# SensorBoard_WiiCam.net
KiCad netlist of a schematic drawn in EAGLE
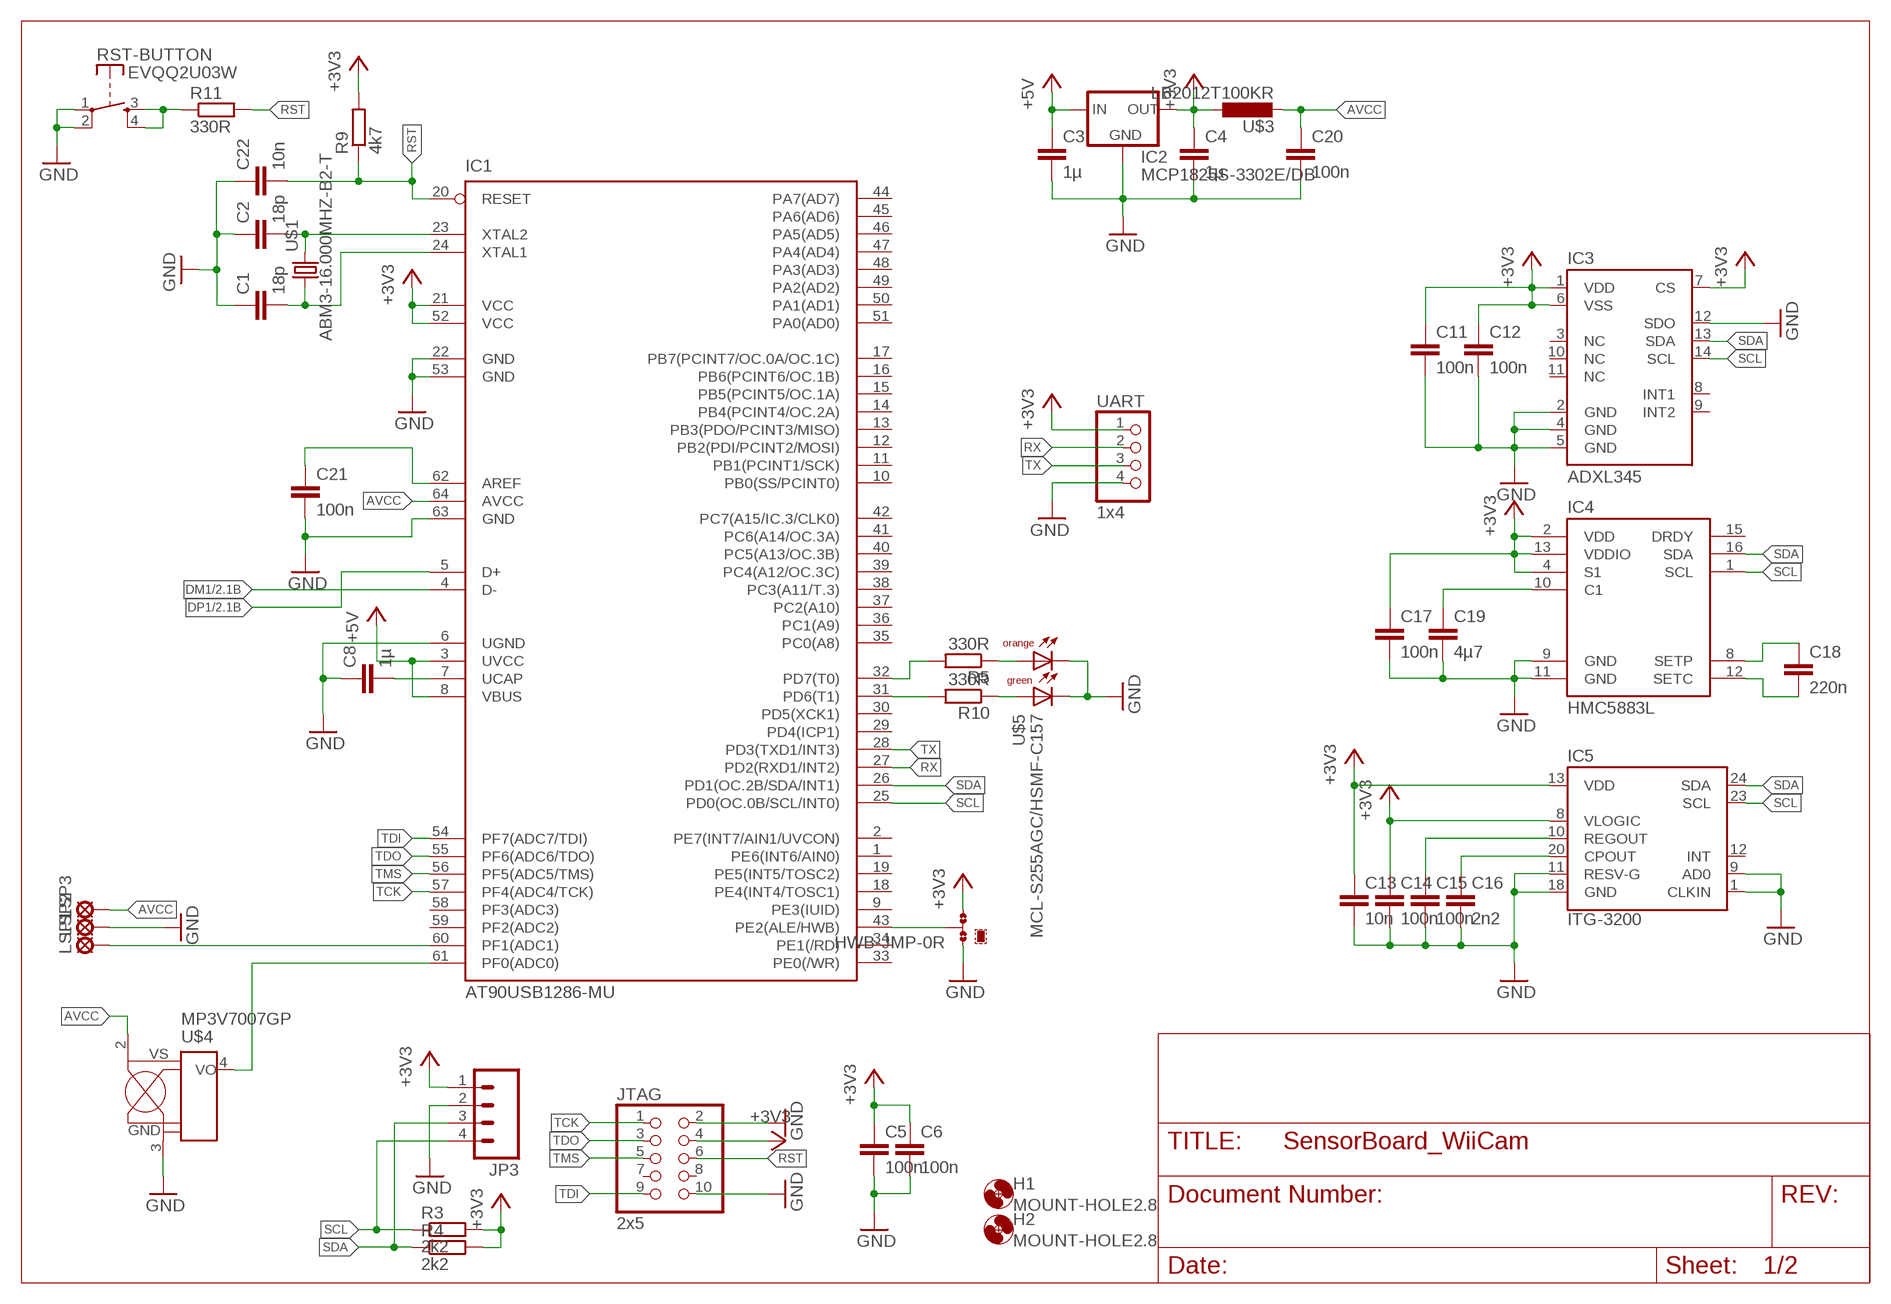
[diagram p0: schematic, sheet 1]
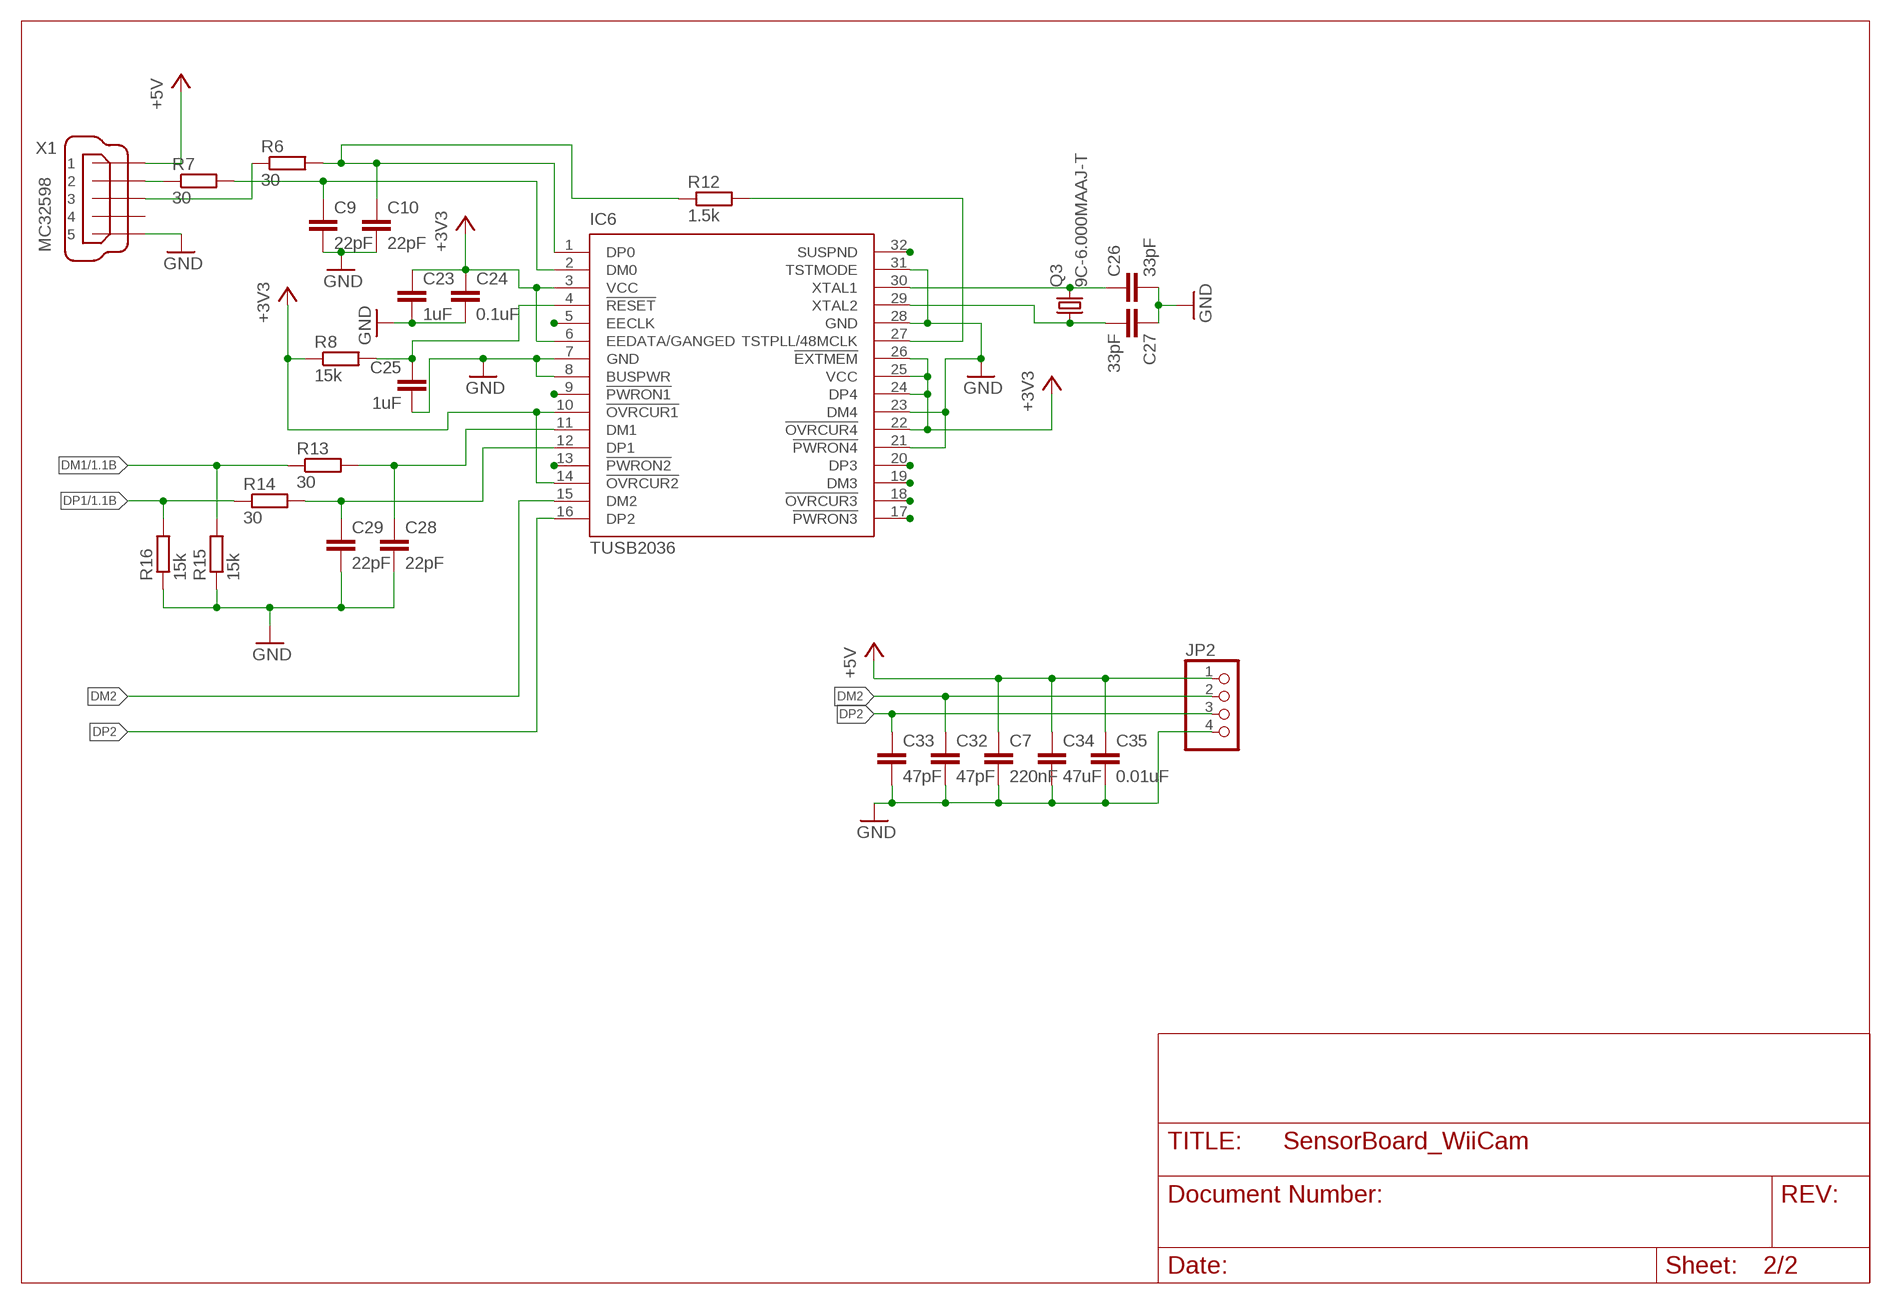
[diagram p1: schematic, sheet 2]

(export (version "E")
  (design (tool "Eeschema 10.0.6"))
  (components
    (comp (ref "C1")
      (value "18p")
      (footprint "eagle-import:C0603K")
      (libsource (lib "eagle-import") (part "C-EUC0603K"))
    )
    (comp (ref "C2")
      (value "18p")
      (footprint "eagle-import:C0603K")
      (libsource (lib "eagle-import") (part "C-EUC0603K"))
    )
    (comp (ref "C3")
      (value "1µ")
      (footprint "eagle-import:C0603K")
      (libsource (lib "eagle-import") (part "C-EUC0603K"))
    )
    (comp (ref "C4")
      (value "1µ")
      (footprint "eagle-import:C0603K")
      (libsource (lib "eagle-import") (part "C-EUC0603K"))
    )
    (comp (ref "C5")
      (value "100n")
      (footprint "eagle-import:C0603K")
      (libsource (lib "eagle-import") (part "C-EUC0603K"))
    )
    (comp (ref "C6")
      (value "100n")
      (footprint "eagle-import:C0603K")
      (libsource (lib "eagle-import") (part "C-EUC0603K"))
    )
    (comp (ref "C8")
      (value "1µ")
      (footprint "eagle-import:C0603K")
      (libsource (lib "eagle-import") (part "C-EUC0603K"))
    )
    (comp (ref "C11")
      (value "100n")
      (footprint "eagle-import:C0603K")
      (libsource (lib "eagle-import") (part "C-EUC0603K"))
    )
    (comp (ref "C12")
      (value "100n")
      (footprint "eagle-import:C0603K")
      (libsource (lib "eagle-import") (part "C-EUC0603K"))
    )
    (comp (ref "C13")
      (value "10n")
      (footprint "eagle-import:C0603K")
      (libsource (lib "eagle-import") (part "C-EUC0603K"))
    )
    (comp (ref "C14")
      (value "100n")
      (footprint "eagle-import:C0603K")
      (libsource (lib "eagle-import") (part "C-EUC0603K"))
    )
    (comp (ref "C15")
      (value "100n")
      (footprint "eagle-import:C0603K")
      (libsource (lib "eagle-import") (part "C-EUC0603K"))
    )
    (comp (ref "C16")
      (value "2n2")
      (footprint "eagle-import:C0603K")
      (libsource (lib "eagle-import") (part "C-EUC0603K"))
    )
    (comp (ref "C17")
      (value "100n")
      (footprint "eagle-import:C0603K")
      (libsource (lib "eagle-import") (part "C-EUC0603K"))
    )
    (comp (ref "C18")
      (value "220n")
      (footprint "eagle-import:C0603K")
      (libsource (lib "eagle-import") (part "C-EUC0603K"))
    )
    (comp (ref "C19")
      (value "4µ7")
      (footprint "eagle-import:C0603K")
      (libsource (lib "eagle-import") (part "C-EUC0603K"))
    )
    (comp (ref "C20")
      (value "100n")
      (footprint "eagle-import:C0603K")
      (libsource (lib "eagle-import") (part "C-EUC0603K"))
    )
    (comp (ref "C21")
      (value "100n")
      (footprint "eagle-import:C0603K")
      (libsource (lib "eagle-import") (part "C-EUC0603K"))
    )
    (comp (ref "C22")
      (value "10n")
      (footprint "eagle-import:C0603K")
      (libsource (lib "eagle-import") (part "C-EUC0603K"))
    )
    (comp (ref "H1")
      (value "MOUNT-HOLE2.8")
      (footprint "eagle-import:2,8")
      (libsource (lib "eagle-import") (part "MOUNT-HOLE2.8"))
    )
    (comp (ref "H2")
      (value "MOUNT-HOLE2.8")
      (footprint "eagle-import:2,8")
      (libsource (lib "eagle-import") (part "MOUNT-HOLE2.8"))
    )
    (comp (ref "HWB-JMP")
      (value "0R-JUMPB")
      (footprint "eagle-import:B0R-JMP")
      (libsource (lib "eagle-import") (part "0R-JUMPB"))
    )
    (comp (ref "IC1")
      (value "AT90USB1286-MU")
      (footprint "eagle-import:TQFP64")
      (libsource (lib "eagle-import") (part "AT90USB1287-AU"))
    )
    (comp (ref "IC2")
      (value "MCP1825S-3302E/DB")
      (footprint "eagle-import:SOT223")
      (libsource (lib "eagle-import") (part "MCP1825-SOT223"))
    )
    (comp (ref "IC3")
      (value "ADXL345")
      (footprint "eagle-import:LGA14")
      (libsource (lib "eagle-import") (part "ADXL345"))
    )
    (comp (ref "IC4")
      (value "HMC5883L")
      (footprint "eagle-import:LPCC16")
      (libsource (lib "eagle-import") (part "HMC5883L"))
    )
    (comp (ref "IC5")
      (value "ITG-3200")
      (footprint "eagle-import:QFN-24")
      (libsource (lib "eagle-import") (part "ITG-3200"))
    )
    (comp (ref "JP3")
      (value "M04PTH")
      (footprint "eagle-import:1X04")
      (libsource (lib "eagle-import") (part "M04PTH"))
    )
    (comp (ref "JTAG")
      (value "2x5")
      (footprint "eagle-import:2X05")
      (libsource (lib "eagle-import") (part "PINHD-2X5"))
    )
    (comp (ref "LSP1")
      (value "NC")
      (footprint "eagle-import:SE14")
      (libsource (lib "eagle-import") (part "SE14"))
    )
    (comp (ref "LSP2")
      (value "NC")
      (footprint "eagle-import:SE14")
      (libsource (lib "eagle-import") (part "SE14"))
    )
    (comp (ref "LSP3")
      (value "NC")
      (footprint "eagle-import:SE14")
      (libsource (lib "eagle-import") (part "SE14"))
    )
    (comp (ref "R3")
      (value "2k2")
      (footprint "eagle-import:R0603")
      (libsource (lib "eagle-import") (part "R-EU_R0603"))
    )
    (comp (ref "R4")
      (value "2k2")
      (footprint "eagle-import:R0603")
      (libsource (lib "eagle-import") (part "R-EU_R0603"))
    )
    (comp (ref "R5")
      (value "330R")
      (footprint "eagle-import:R0603")
      (libsource (lib "eagle-import") (part "R-EU_R0603"))
    )
    (comp (ref "R9")
      (value "4k7")
      (footprint "eagle-import:R0603")
      (libsource (lib "eagle-import") (part "R-EU_R0603"))
    )
    (comp (ref "R10")
      (value "330R")
      (footprint "eagle-import:R0603")
      (libsource (lib "eagle-import") (part "R-EU_R0603"))
    )
    (comp (ref "R11")
      (value "330R")
      (footprint "eagle-import:R0603")
      (libsource (lib "eagle-import") (part "R-EU_R0603"))
    )
    (comp (ref "RST-BUTTON")
      (value "EVQQ2U03W")
      (footprint "eagle-import:EVQQ2")
      (libsource (lib "eagle-import") (part "SWITCH-SPNO"))
    )
    (comp (ref "U$1")
      (value "ABM3-16.000MHZ-B2-T")
      (footprint "eagle-import:SMD_5X3.2MM")
      (libsource (lib "eagle-import") (part "TXC_ABM3"))
    )
    (comp (ref "U$3")
      (value "LB2012T100KR")
      (footprint "eagle-import:L-2012")
      (libsource (lib "eagle-import") (part "L-TAIYO-YUDEN"))
    )
    (comp (ref "U$4")
      (value "MP3V7007GP")
      (footprint "eagle-import:SOP-8")
      (libsource (lib "eagle-import") (part "MP3V7007GP"))
    )
    (comp (ref "U$5")
      (value "MCL-S255AGC/HSMF-C157")
      (footprint "eagle-import:DUOLED-1210")
      (libsource (lib "eagle-import") (part "DUOLED-MULTICOMP"))
    )
    (comp (ref "UART")
      (value "1x4")
      (footprint "eagle-import:1X04")
      (libsource (lib "eagle-import") (part "PINHD-1X4"))
    )
    (comp (ref "C7")
      (value "220nF")
      (footprint "eagle-import:C0603")
      (libsource (lib "eagle-import") (part "C-EUC0603"))
    )
    (comp (ref "C9")
      (value "22pF")
      (footprint "eagle-import:C0603")
      (libsource (lib "eagle-import") (part "C-EUC0603"))
    )
    (comp (ref "C10")
      (value "22pF")
      (footprint "eagle-import:C0603")
      (libsource (lib "eagle-import") (part "C-EUC0603"))
    )
    (comp (ref "C23")
      (value "1uF")
      (footprint "eagle-import:C0603")
      (libsource (lib "eagle-import") (part "C-EUC0603"))
    )
    (comp (ref "C24")
      (value "0.1uF")
      (footprint "eagle-import:C0603")
      (libsource (lib "eagle-import") (part "C-EUC0603"))
    )
    (comp (ref "C25")
      (value "1uF")
      (footprint "eagle-import:C0603")
      (libsource (lib "eagle-import") (part "C-EUC0603"))
    )
    (comp (ref "C26")
      (value "33pF")
      (footprint "eagle-import:C0603")
      (libsource (lib "eagle-import") (part "C-EUC0603"))
    )
    (comp (ref "C27")
      (value "33pF")
      (footprint "eagle-import:C0603")
      (libsource (lib "eagle-import") (part "C-EUC0603"))
    )
    (comp (ref "C28")
      (value "22pF")
      (footprint "eagle-import:C0603")
      (libsource (lib "eagle-import") (part "C-EUC0603"))
    )
    (comp (ref "C29")
      (value "22pF")
      (footprint "eagle-import:C0603")
      (libsource (lib "eagle-import") (part "C-EUC0603"))
    )
    (comp (ref "C32")
      (value "47pF")
      (footprint "eagle-import:C0603")
      (libsource (lib "eagle-import") (part "C-EUC0603"))
    )
    (comp (ref "C33")
      (value "47pF")
      (footprint "eagle-import:C0603")
      (libsource (lib "eagle-import") (part "C-EUC0603"))
    )
    (comp (ref "C34")
      (value "47uF")
      (footprint "eagle-import:C0805")
      (libsource (lib "eagle-import") (part "C-EUC0805"))
    )
    (comp (ref "C35")
      (value "0.01uF")
      (footprint "eagle-import:C0603")
      (libsource (lib "eagle-import") (part "C-EUC0603"))
    )
    (comp (ref "IC6")
      (value "TUSB2036")
      (footprint "eagle-import:VF_S-PQFP-G32")
      (fields (field (name "MF") "TEXAS INSTRUMENTS") (field (name "MPN") "TUSB2046BVFR"))
      (libsource (lib "eagle-import") (part "TUSB2046BVFR"))
    )
    (comp (ref "JP2")
      (value "PINHD-1X4")
      (footprint "eagle-import:1X04")
      (libsource (lib "eagle-import") (part "PINHD-1X4"))
    )
    (comp (ref "Q3")
      (value "9C-6.000MAAJ-T")
      (footprint "eagle-import:CSM-7X-DU")
      (libsource (lib "eagle-import") (part "CSM-7X-DU"))
    )
    (comp (ref "R6")
      (value "30")
      (footprint "eagle-import:R0603")
      (libsource (lib "eagle-import") (part "R-EU_R0603"))
    )
    (comp (ref "R7")
      (value "30")
      (footprint "eagle-import:R0603")
      (libsource (lib "eagle-import") (part "R-EU_R0603"))
    )
    (comp (ref "R8")
      (value "15k")
      (footprint "eagle-import:R0603")
      (libsource (lib "eagle-import") (part "R-EU_R0603"))
    )
    (comp (ref "R12")
      (value "1.5k")
      (footprint "eagle-import:R0603")
      (libsource (lib "eagle-import") (part "R-EU_R0603"))
    )
    (comp (ref "R13")
      (value "30")
      (footprint "eagle-import:R0603")
      (libsource (lib "eagle-import") (part "R-EU_R0603"))
    )
    (comp (ref "R14")
      (value "30")
      (footprint "eagle-import:R0603")
      (libsource (lib "eagle-import") (part "R-EU_R0603"))
    )
    (comp (ref "R15")
      (value "15k")
      (footprint "eagle-import:R0603")
      (libsource (lib "eagle-import") (part "R-EU_R0603"))
    )
    (comp (ref "R16")
      (value "15k")
      (footprint "eagle-import:R0603")
      (libsource (lib "eagle-import") (part "R-EU_R0603"))
    )
    (comp (ref "X1")
      (value "MC32598")
      (footprint "eagle-import:32005-201")
      (libsource (lib "eagle-import") (part "MINI-USB-32005-201"))
    )
  )
  (nets
    (net (code "1") (name "+3V3") (class "Default")
      (node (ref "C11") (pin "1") (pinfunction "1_1") (pintype "passive"))
      (node (ref "C12") (pin "1") (pinfunction "1_1") (pintype "passive"))
      (node (ref "C13") (pin "1") (pinfunction "1_1") (pintype "passive"))
      (node (ref "C14") (pin "1") (pinfunction "1_1") (pintype "passive"))
      (node (ref "C17") (pin "1") (pinfunction "1_1") (pintype "passive"))
      (node (ref "C23") (pin "1") (pinfunction "1_1") (pintype "passive"))
      (node (ref "C24") (pin "1") (pinfunction "1_1") (pintype "passive"))
      (node (ref "C4") (pin "1") (pinfunction "1_1") (pintype "passive"))
      (node (ref "C5") (pin "1") (pinfunction "1_1") (pintype "passive"))
      (node (ref "C6") (pin "1") (pinfunction "1_1") (pintype "passive"))
      (node (ref "HWB-JMP") (pin "3") (pinfunction "3_3") (pintype "passive"))
      (node (ref "IC1") (pin "21") (pinfunction "VCC_21") (pintype "power_in"))
      (node (ref "IC1") (pin "52") (pinfunction "VCC_52") (pintype "power_in"))
      (node (ref "IC2") (pin "3") (pinfunction "OUT_3") (pintype "passive"))
      (node (ref "IC3") (pin "1") (pinfunction "VDD_1") (pintype "bidirectional"))
      (node (ref "IC3") (pin "6") (pinfunction "VSS_6") (pintype "bidirectional"))
      (node (ref "IC3") (pin "7") (pinfunction "CS_7") (pintype "bidirectional"))
      (node (ref "IC4") (pin "13") (pinfunction "VDDIO_13") (pintype "bidirectional"))
      (node (ref "IC4") (pin "2") (pinfunction "VDD_2") (pintype "bidirectional"))
      (node (ref "IC4") (pin "4") (pinfunction "S1_4") (pintype "bidirectional"))
      (node (ref "IC5") (pin "13") (pinfunction "VDD_13") (pintype "bidirectional"))
      (node (ref "IC5") (pin "8") (pinfunction "VLOGIC_8") (pintype "bidirectional"))
      (node (ref "IC6") (pin "10") (pinfunction "~{OVRCUR1}_10") (pintype "input"))
      (node (ref "IC6") (pin "14") (pinfunction "~{OVRCUR2}_14") (pintype "input"))
      (node (ref "IC6") (pin "22") (pinfunction "~{OVRCUR4}_22") (pintype "input"))
      (node (ref "IC6") (pin "24") (pinfunction "DP4_24") (pintype "bidirectional"))
      (node (ref "IC6") (pin "25") (pinfunction "VCC_25") (pintype "power_in"))
      (node (ref "IC6") (pin "26") (pinfunction "~{EXTMEM}_26") (pintype "input"))
      (node (ref "IC6") (pin "3") (pinfunction "VCC_3") (pintype "power_in"))
      (node (ref "IC6") (pin "6") (pinfunction "EEDATA/GANGED_6") (pintype "bidirectional"))
      (node (ref "JP3") (pin "1") (pinfunction "1_1") (pintype "passive"))
      (node (ref "JTAG") (pin "4") (pinfunction "4_4") (pintype "passive"))
      (node (ref "R3") (pin "2") (pinfunction "2_2") (pintype "passive"))
      (node (ref "R4") (pin "2") (pinfunction "2_2") (pintype "passive"))
      (node (ref "R8") (pin "1") (pinfunction "1_1") (pintype "passive"))
      (node (ref "R9") (pin "2") (pinfunction "2_2") (pintype "passive"))
      (node (ref "U$3") (pin "1") (pinfunction "1_1") (pintype "passive"))
      (node (ref "UART") (pin "1") (pinfunction "1_1") (pintype "passive"))
    )
    (net (code "2") (name "+5V") (class "Default")
      (node (ref "C3") (pin "1") (pinfunction "1_1") (pintype "passive"))
      (node (ref "C34") (pin "1") (pinfunction "1_1") (pintype "passive"))
      (node (ref "C35") (pin "1") (pinfunction "1_1") (pintype "passive"))
      (node (ref "C7") (pin "1") (pinfunction "1_1") (pintype "passive"))
      (node (ref "IC1") (pin "3") (pinfunction "UVCC_3") (pintype "power_in"))
      (node (ref "IC1") (pin "8") (pinfunction "VBUS_8") (pintype "power_in"))
      (node (ref "IC2") (pin "1") (pinfunction "IN_1") (pintype "input"))
      (node (ref "JP2") (pin "1") (pinfunction "1_1") (pintype "passive"))
      (node (ref "X1") (pin "1") (pinfunction "1_1") (pintype "passive"))
    )
    (net (code "3") (name "AVCC") (class "Default")
      (node (ref "C20") (pin "1") (pinfunction "1_1") (pintype "passive"))
      (node (ref "IC1") (pin "64") (pinfunction "AVCC_64") (pintype "bidirectional"))
      (node (ref "LSP3") (pin "MP") (pinfunction "MP_MP") (pintype "passive"))
      (node (ref "U$3") (pin "2") (pinfunction "2_2") (pintype "passive"))
      (node (ref "U$4") (pin "2") (pinfunction "VS_2") (pintype "passive"))
    )
    (net (code "4") (name "DM1") (class "Default")
      (node (ref "IC1") (pin "4") (pinfunction "D-_4") (pintype "bidirectional"))
      (node (ref "R13") (pin "1") (pinfunction "1_1") (pintype "passive"))
      (node (ref "R15") (pin "2") (pinfunction "2_2") (pintype "passive"))
    )
    (net (code "5") (name "DM2") (class "Default")
      (node (ref "C32") (pin "1") (pinfunction "1_1") (pintype "passive"))
      (node (ref "IC6") (pin "15") (pinfunction "DM2_15") (pintype "bidirectional"))
      (node (ref "JP2") (pin "2") (pinfunction "2_2") (pintype "passive"))
    )
    (net (code "6") (name "DP1") (class "Default")
      (node (ref "IC1") (pin "5") (pinfunction "D+_5") (pintype "bidirectional"))
      (node (ref "R14") (pin "1") (pinfunction "1_1") (pintype "passive"))
      (node (ref "R16") (pin "2") (pinfunction "2_2") (pintype "passive"))
    )
    (net (code "7") (name "DP2") (class "Default")
      (node (ref "C33") (pin "1") (pinfunction "1_1") (pintype "passive"))
      (node (ref "IC6") (pin "16") (pinfunction "DP2_16") (pintype "bidirectional"))
      (node (ref "JP2") (pin "3") (pinfunction "3_3") (pintype "passive"))
    )
    (net (code "8") (name "GND") (class "Default")
      (node (ref "C1") (pin "1") (pinfunction "1_1") (pintype "passive"))
      (node (ref "C10") (pin "2") (pinfunction "2_2") (pintype "passive"))
      (node (ref "C11") (pin "2") (pinfunction "2_2") (pintype "passive"))
      (node (ref "C12") (pin "2") (pinfunction "2_2") (pintype "passive"))
      (node (ref "C13") (pin "2") (pinfunction "2_2") (pintype "passive"))
      (node (ref "C14") (pin "2") (pinfunction "2_2") (pintype "passive"))
      (node (ref "C15") (pin "2") (pinfunction "2_2") (pintype "passive"))
      (node (ref "C16") (pin "2") (pinfunction "2_2") (pintype "passive"))
      (node (ref "C17") (pin "2") (pinfunction "2_2") (pintype "passive"))
      (node (ref "C19") (pin "2") (pinfunction "2_2") (pintype "passive"))
      (node (ref "C2") (pin "1") (pinfunction "1_1") (pintype "passive"))
      (node (ref "C20") (pin "2") (pinfunction "2_2") (pintype "passive"))
      (node (ref "C21") (pin "2") (pinfunction "2_2") (pintype "passive"))
      (node (ref "C22") (pin "1") (pinfunction "1_1") (pintype "passive"))
      (node (ref "C23") (pin "2") (pinfunction "2_2") (pintype "passive"))
      (node (ref "C24") (pin "2") (pinfunction "2_2") (pintype "passive"))
      (node (ref "C25") (pin "2") (pinfunction "2_2") (pintype "passive"))
      (node (ref "C26") (pin "2") (pinfunction "2_2") (pintype "passive"))
      (node (ref "C27") (pin "1") (pinfunction "1_1") (pintype "passive"))
      (node (ref "C28") (pin "2") (pinfunction "2_2") (pintype "passive"))
      (node (ref "C29") (pin "2") (pinfunction "2_2") (pintype "passive"))
      (node (ref "C3") (pin "2") (pinfunction "2_2") (pintype "passive"))
      (node (ref "C32") (pin "2") (pinfunction "2_2") (pintype "passive"))
      (node (ref "C33") (pin "2") (pinfunction "2_2") (pintype "passive"))
      (node (ref "C34") (pin "2") (pinfunction "2_2") (pintype "passive"))
      (node (ref "C35") (pin "2") (pinfunction "2_2") (pintype "passive"))
      (node (ref "C4") (pin "2") (pinfunction "2_2") (pintype "passive"))
      (node (ref "C5") (pin "2") (pinfunction "2_2") (pintype "passive"))
      (node (ref "C6") (pin "2") (pinfunction "2_2") (pintype "passive"))
      (node (ref "C7") (pin "2") (pinfunction "2_2") (pintype "passive"))
      (node (ref "C8") (pin "1") (pinfunction "1_1") (pintype "passive"))
      (node (ref "C9") (pin "2") (pinfunction "2_2") (pintype "passive"))
      (node (ref "HWB-JMP") (pin "1") (pinfunction "1_1") (pintype "passive"))
      (node (ref "IC1") (pin "22") (pinfunction "GND_22") (pintype "power_in"))
      (node (ref "IC1") (pin "53") (pinfunction "GND_53") (pintype "power_in"))
      (node (ref "IC1") (pin "6") (pinfunction "UGND_6") (pintype "power_in"))
      (node (ref "IC1") (pin "63") (pinfunction "GND_63") (pintype "power_in"))
      (node (ref "IC2") (pin "2") (pinfunction "GND_2") (pintype "input"))
      (node (ref "IC2") (pin "4") (pinfunction "GND_4") (pintype "input"))
      (node (ref "IC3") (pin "12") (pinfunction "SDO_12") (pintype "bidirectional"))
      (node (ref "IC3") (pin "2") (pinfunction "GND_2") (pintype "bidirectional"))
      (node (ref "IC3") (pin "4") (pinfunction "GND_4") (pintype "bidirectional"))
      (node (ref "IC3") (pin "5") (pinfunction "GND_5") (pintype "bidirectional"))
      (node (ref "IC4") (pin "11") (pinfunction "GND_11") (pintype "bidirectional"))
      (node (ref "IC4") (pin "9") (pinfunction "GND_9") (pintype "bidirectional"))
      (node (ref "IC5") (pin "1") (pinfunction "CLKIN_1") (pintype "bidirectional"))
      (node (ref "IC5") (pin "11") (pinfunction "RESV-G_11") (pintype "bidirectional"))
      (node (ref "IC5") (pin "18") (pinfunction "GND_18") (pintype "bidirectional"))
      (node (ref "IC5") (pin "9") (pinfunction "AD0_9") (pintype "bidirectional"))
      (node (ref "IC6") (pin "21") (pinfunction "~{PWRON4}_21") (pintype "output"))
      (node (ref "IC6") (pin "23") (pinfunction "DM4_23") (pintype "bidirectional"))
      (node (ref "IC6") (pin "28") (pinfunction "GND_28") (pintype "power_in"))
      (node (ref "IC6") (pin "31") (pinfunction "TSTMODE_31") (pintype "input"))
      (node (ref "IC6") (pin "7") (pinfunction "GND_7") (pintype "power_in"))
      (node (ref "IC6") (pin "8") (pinfunction "BUSPWR_8") (pintype "input"))
      (node (ref "JP2") (pin "4") (pinfunction "4_4") (pintype "passive"))
      (node (ref "JP3") (pin "2") (pinfunction "2_2") (pintype "passive"))
      (node (ref "JTAG") (pin "10") (pinfunction "10_10") (pintype "passive"))
      (node (ref "JTAG") (pin "2") (pinfunction "2_2") (pintype "passive"))
      (node (ref "LSP2") (pin "MP") (pinfunction "MP_MP") (pintype "passive"))
      (node (ref "R15") (pin "1") (pinfunction "1_1") (pintype "passive"))
      (node (ref "R16") (pin "1") (pinfunction "1_1") (pintype "passive"))
      (node (ref "RST-BUTTON") (pin "1") (pinfunction "P_1") (pintype "passive"))
      (node (ref "RST-BUTTON") (pin "2") (pinfunction "P_2") (pintype "passive"))
      (node (ref "U$4") (pin "3") (pinfunction "GND_3") (pintype "passive"))
      (node (ref "U$5") (pin "1") (pinfunction "C_1") (pintype "passive"))
      (node (ref "U$5") (pin "2") (pinfunction "C_2") (pintype "passive"))
      (node (ref "UART") (pin "4") (pinfunction "4_4") (pintype "passive"))
      (node (ref "X1") (pin "5") (pinfunction "5_5") (pintype "passive"))
    )
    (net (code "9") (name "Net-(IC1-AREF)") (class "Default")
      (node (ref "C21") (pin "1") (pinfunction "1_1") (pintype "passive"))
      (node (ref "IC1") (pin "62") (pinfunction "AREF_62") (pintype "bidirectional"))
    )
    (net (code "10") (name "Net-(IC1-PD6(T1))") (class "Default")
      (node (ref "IC1") (pin "31") (pinfunction "PD6(T1)_31") (pintype "bidirectional"))
      (node (ref "R10") (pin "2") (pinfunction "2_2") (pintype "passive"))
    )
    (net (code "11") (name "Net-(IC1-PD7(T0))") (class "Default")
      (node (ref "IC1") (pin "32") (pinfunction "PD7(T0)_32") (pintype "bidirectional"))
      (node (ref "R5") (pin "2") (pinfunction "2_2") (pintype "passive"))
    )
    (net (code "12") (name "Net-(IC1-PE2(ALE{slash}HWB))") (class "Default")
      (node (ref "HWB-JMP") (pin "2") (pinfunction "2_2") (pintype "passive"))
      (node (ref "IC1") (pin "43") (pinfunction "PE2(ALE/HWB)_43") (pintype "bidirectional"))
    )
    (net (code "13") (name "Net-(IC1-PF0(ADC0))") (class "Default")
      (node (ref "IC1") (pin "61") (pinfunction "PF0(ADC0)_61") (pintype "bidirectional"))
      (node (ref "U$4") (pin "4") (pinfunction "OUT_4") (pintype "passive"))
    )
    (net (code "14") (name "Net-(IC1-PF1(ADC1))") (class "Default")
      (node (ref "IC1") (pin "60") (pinfunction "PF1(ADC1)_60") (pintype "bidirectional"))
      (node (ref "LSP1") (pin "MP") (pinfunction "MP_MP") (pintype "passive"))
    )
    (net (code "15") (name "Net-(IC1-UCAP)") (class "Default")
      (node (ref "C8") (pin "2") (pinfunction "2_2") (pintype "passive"))
      (node (ref "IC1") (pin "7") (pinfunction "UCAP_7") (pintype "power_in"))
    )
    (net (code "16") (name "Net-(IC1-XTAL1)") (class "Default")
      (node (ref "C1") (pin "2") (pinfunction "2_2") (pintype "passive"))
      (node (ref "IC1") (pin "24") (pinfunction "XTAL1_24") (pintype "bidirectional"))
      (node (ref "U$1") (pin "P$1") (pinfunction "1_P$1") (pintype "passive"))
    )
    (net (code "17") (name "Net-(IC1-XTAL2)") (class "Default")
      (node (ref "C2") (pin "2") (pinfunction "2_2") (pintype "passive"))
      (node (ref "IC1") (pin "23") (pinfunction "XTAL2_23") (pintype "bidirectional"))
      (node (ref "U$1") (pin "P$2") (pinfunction "2_P$2") (pintype "passive"))
    )
    (net (code "18") (name "Net-(IC4-C1)") (class "Default")
      (node (ref "C19") (pin "1") (pinfunction "1_1") (pintype "passive"))
      (node (ref "IC4") (pin "10") (pinfunction "C1_10") (pintype "bidirectional"))
    )
    (net (code "19") (name "Net-(IC4-SETC)") (class "Default")
      (node (ref "C18") (pin "2") (pinfunction "2_2") (pintype "passive"))
      (node (ref "IC4") (pin "12") (pinfunction "SETC_12") (pintype "bidirectional"))
    )
    (net (code "20") (name "Net-(IC4-SETP)") (class "Default")
      (node (ref "C18") (pin "1") (pinfunction "1_1") (pintype "passive"))
      (node (ref "IC4") (pin "8") (pinfunction "SETP_8") (pintype "bidirectional"))
    )
    (net (code "21") (name "Net-(IC5-CPOUT)") (class "Default")
      (node (ref "C16") (pin "1") (pinfunction "1_1") (pintype "passive"))
      (node (ref "IC5") (pin "20") (pinfunction "CPOUT_20") (pintype "bidirectional"))
    )
    (net (code "22") (name "Net-(IC5-REGOUT)") (class "Default")
      (node (ref "C15") (pin "1") (pinfunction "1_1") (pintype "passive"))
      (node (ref "IC5") (pin "10") (pinfunction "REGOUT_10") (pintype "bidirectional"))
    )
    (net (code "23") (name "Net-(IC6-DM0)") (class "Default")
      (node (ref "C9") (pin "1") (pinfunction "1_1") (pintype "passive"))
      (node (ref "IC6") (pin "2") (pinfunction "DM0_2") (pintype "bidirectional"))
      (node (ref "R7") (pin "2") (pinfunction "2_2") (pintype "passive"))
    )
    (net (code "24") (name "Net-(IC6-DM1)") (class "Default")
      (node (ref "C28") (pin "1") (pinfunction "1_1") (pintype "passive"))
      (node (ref "IC6") (pin "11") (pinfunction "DM1_11") (pintype "bidirectional"))
      (node (ref "R13") (pin "2") (pinfunction "2_2") (pintype "passive"))
    )
    (net (code "25") (name "Net-(IC6-DP0)") (class "Default")
      (node (ref "C10") (pin "1") (pinfunction "1_1") (pintype "passive"))
      (node (ref "IC6") (pin "1") (pinfunction "DP0_1") (pintype "bidirectional"))
      (node (ref "R12") (pin "1") (pinfunction "1_1") (pintype "passive"))
      (node (ref "R6") (pin "2") (pinfunction "2_2") (pintype "passive"))
    )
    (net (code "26") (name "Net-(IC6-DP1)") (class "Default")
      (node (ref "C29") (pin "1") (pinfunction "1_1") (pintype "passive"))
      (node (ref "IC6") (pin "12") (pinfunction "DP1_12") (pintype "bidirectional"))
      (node (ref "R14") (pin "2") (pinfunction "2_2") (pintype "passive"))
    )
    (net (code "27") (name "Net-(IC6-TSTPLL{slash}48MCLK)") (class "Default")
      (node (ref "IC6") (pin "27") (pinfunction "TSTPLL/48MCLK_27") (pintype "bidirectional"))
      (node (ref "R12") (pin "2") (pinfunction "2_2") (pintype "passive"))
    )
    (net (code "28") (name "Net-(IC6-XTAL1)") (class "Default")
      (node (ref "C26") (pin "1") (pinfunction "1_1") (pintype "passive"))
      (node (ref "IC6") (pin "30") (pinfunction "XTAL1_30") (pintype "input"))
      (node (ref "Q3") (pin "2") (pinfunction "2_2") (pintype "passive"))
    )
    (net (code "29") (name "Net-(IC6-XTAL2)") (class "Default")
      (node (ref "C27") (pin "2") (pinfunction "2_2") (pintype "passive"))
      (node (ref "IC6") (pin "29") (pinfunction "XTAL2_29") (pintype "output"))
      (node (ref "Q3") (pin "1") (pinfunction "1_1") (pintype "passive"))
    )
    (net (code "30") (name "Net-(IC6-~{RESET})") (class "Default")
      (node (ref "C25") (pin "1") (pinfunction "1_1") (pintype "passive"))
      (node (ref "IC6") (pin "4") (pinfunction "~{RESET}_4") (pintype "input"))
      (node (ref "R8") (pin "2") (pinfunction "2_2") (pintype "passive"))
    )
    (net (code "31") (name "Net-(R6-Pad1)") (class "Default")
      (node (ref "R6") (pin "1") (pinfunction "1_1") (pintype "passive"))
      (node (ref "X1") (pin "3") (pinfunction "3_3") (pintype "passive"))
    )
    (net (code "32") (name "Net-(R7-Pad1)") (class "Default")
      (node (ref "R7") (pin "1") (pinfunction "1_1") (pintype "passive"))
      (node (ref "X1") (pin "2") (pinfunction "2_2") (pintype "passive"))
    )
    (net (code "33") (name "Net-(R11-Pad1)") (class "Default")
      (node (ref "R11") (pin "1") (pinfunction "1_1") (pintype "passive"))
      (node (ref "RST-BUTTON") (pin "3") (pinfunction "S_3") (pintype "passive"))
      (node (ref "RST-BUTTON") (pin "4") (pinfunction "S_4") (pintype "passive"))
    )
    (net (code "34") (name "Net-(U$5-AG)") (class "Default")
      (node (ref "R10") (pin "1") (pinfunction "1_1") (pintype "passive"))
      (node (ref "U$5") (pin "3") (pinfunction "AG_3") (pintype "passive"))
    )
    (net (code "35") (name "Net-(U$5-AO)") (class "Default")
      (node (ref "R5") (pin "1") (pinfunction "1_1") (pintype "passive"))
      (node (ref "U$5") (pin "4") (pinfunction "AO_4") (pintype "passive"))
    )
    (net (code "36") (name "RST") (class "Default")
      (node (ref "C22") (pin "2") (pinfunction "2_2") (pintype "passive"))
      (node (ref "IC1") (pin "20") (pinfunction "RESET_20") (pintype "input"))
      (node (ref "JTAG") (pin "6") (pinfunction "6_6") (pintype "passive"))
      (node (ref "R11") (pin "2") (pinfunction "2_2") (pintype "passive"))
      (node (ref "R9") (pin "1") (pinfunction "1_1") (pintype "passive"))
    )
    (net (code "37") (name "RX") (class "Default")
      (node (ref "IC1") (pin "27") (pinfunction "PD2(RXD1/INT2)_27") (pintype "bidirectional"))
      (node (ref "UART") (pin "2") (pinfunction "2_2") (pintype "passive"))
    )
    (net (code "38") (name "SCL") (class "Default")
      (node (ref "IC1") (pin "25") (pinfunction "PD0(OC.0B/SCL/INT0)_25") (pintype "bidirectional"))
      (node (ref "IC3") (pin "14") (pinfunction "SCL_14") (pintype "bidirectional"))
      (node (ref "IC4") (pin "1") (pinfunction "SCL_1") (pintype "bidirectional"))
      (node (ref "IC5") (pin "23") (pinfunction "SCL_23") (pintype "bidirectional"))
      (node (ref "JP3") (pin "4") (pinfunction "4_4") (pintype "passive"))
      (node (ref "R3") (pin "1") (pinfunction "1_1") (pintype "passive"))
    )
    (net (code "39") (name "SDA") (class "Default")
      (node (ref "IC1") (pin "26") (pinfunction "PD1(OC.2B/SDA/INT1)_26") (pintype "bidirectional"))
      (node (ref "IC3") (pin "13") (pinfunction "SDA_13") (pintype "bidirectional"))
      (node (ref "IC4") (pin "16") (pinfunction "SDA_16") (pintype "bidirectional"))
      (node (ref "IC5") (pin "24") (pinfunction "SDA_24") (pintype "bidirectional"))
      (node (ref "JP3") (pin "3") (pinfunction "3_3") (pintype "passive"))
      (node (ref "R4") (pin "1") (pinfunction "1_1") (pintype "passive"))
    )
    (net (code "40") (name "TCK") (class "Default")
      (node (ref "IC1") (pin "57") (pinfunction "PF4(ADC4/TCK)_57") (pintype "bidirectional"))
      (node (ref "JTAG") (pin "1") (pinfunction "1_1") (pintype "passive"))
    )
    (net (code "41") (name "TDI") (class "Default")
      (node (ref "IC1") (pin "54") (pinfunction "PF7(ADC7/TDI)_54") (pintype "bidirectional"))
      (node (ref "JTAG") (pin "9") (pinfunction "9_9") (pintype "passive"))
    )
    (net (code "42") (name "TDO") (class "Default")
      (node (ref "IC1") (pin "55") (pinfunction "PF6(ADC6/TDO)_55") (pintype "bidirectional"))
      (node (ref "JTAG") (pin "3") (pinfunction "3_3") (pintype "passive"))
    )
    (net (code "43") (name "TMS") (class "Default")
      (node (ref "IC1") (pin "56") (pinfunction "PF5(ADC5/TMS)_56") (pintype "bidirectional"))
      (node (ref "JTAG") (pin "5") (pinfunction "5_5") (pintype "passive"))
    )
    (net (code "44") (name "TX") (class "Default")
      (node (ref "IC1") (pin "28") (pinfunction "PD3(TXD1/INT3)_28") (pintype "bidirectional"))
      (node (ref "UART") (pin "3") (pinfunction "3_3") (pintype "passive"))
    )
    (net (code "45") (name "unconnected-(IC1-PA0(AD0)-Pad51)") (class "Default")
      (node (ref "IC1") (pin "51") (pinfunction "PA0(AD0)_51") (pintype "bidirectional"))
    )
    (net (code "46") (name "unconnected-(IC1-PA1(AD1)-Pad50)") (class "Default")
      (node (ref "IC1") (pin "50") (pinfunction "PA1(AD1)_50") (pintype "bidirectional"))
    )
    (net (code "47") (name "unconnected-(IC1-PA2(AD2)-Pad49)") (class "Default")
      (node (ref "IC1") (pin "49") (pinfunction "PA2(AD2)_49") (pintype "bidirectional"))
    )
    (net (code "48") (name "unconnected-(IC1-PA3(AD3)-Pad48)") (class "Default")
      (node (ref "IC1") (pin "48") (pinfunction "PA3(AD3)_48") (pintype "bidirectional"))
    )
    (net (code "49") (name "unconnected-(IC1-PA4(AD4)-Pad47)") (class "Default")
      (node (ref "IC1") (pin "47") (pinfunction "PA4(AD4)_47") (pintype "bidirectional"))
    )
    (net (code "50") (name "unconnected-(IC1-PA5(AD5)-Pad46)") (class "Default")
      (node (ref "IC1") (pin "46") (pinfunction "PA5(AD5)_46") (pintype "bidirectional"))
    )
    (net (code "51") (name "unconnected-(IC1-PA6(AD6)-Pad45)") (class "Default")
      (node (ref "IC1") (pin "45") (pinfunction "PA6(AD6)_45") (pintype "bidirectional"))
    )
    (net (code "52") (name "unconnected-(IC1-PA7(AD7)-Pad44)") (class "Default")
      (node (ref "IC1") (pin "44") (pinfunction "PA7(AD7)_44") (pintype "bidirectional"))
    )
    (net (code "53") (name "unconnected-(IC1-PB0(SS{slash}PCINT0)-Pad10)") (class "Default")
      (node (ref "IC1") (pin "10") (pinfunction "PB0(SS/PCINT0)_10") (pintype "bidirectional"))
    )
    (net (code "54") (name "unconnected-(IC1-PB1(PCINT1{slash}SCK)-Pad11)") (class "Default")
      (node (ref "IC1") (pin "11") (pinfunction "PB1(PCINT1/SCK)_11") (pintype "bidirectional"))
    )
    (net (code "55") (name "unconnected-(IC1-PB2(PDI{slash}PCINT2{slash}MOSI)-Pad12)") (class "Default")
      (node (ref "IC1") (pin "12") (pinfunction "PB2(PDI/PCINT2/MOSI)_12") (pintype "bidirectional"))
    )
    (net (code "56") (name "unconnected-(IC1-PB3(PDO{slash}PCINT3{slash}MISO)-Pad13)") (class "Default")
      (node (ref "IC1") (pin "13") (pinfunction "PB3(PDO/PCINT3/MISO)_13") (pintype "bidirectional"))
    )
    (net (code "57") (name "unconnected-(IC1-PB4(PCINT4{slash}OC.2A)-Pad14)") (class "Default")
      (node (ref "IC1") (pin "14") (pinfunction "PB4(PCINT4/OC.2A)_14") (pintype "bidirectional"))
    )
    (net (code "58") (name "unconnected-(IC1-PB5(PCINT5{slash}OC.1A)-Pad15)") (class "Default")
      (node (ref "IC1") (pin "15") (pinfunction "PB5(PCINT5/OC.1A)_15") (pintype "bidirectional"))
    )
    (net (code "59") (name "unconnected-(IC1-PB6(PCINT6{slash}OC.1B)-Pad16)") (class "Default")
      (node (ref "IC1") (pin "16") (pinfunction "PB6(PCINT6/OC.1B)_16") (pintype "bidirectional"))
    )
    (net (code "60") (name "unconnected-(IC1-PB7(PCINT7{slash}OC.0A{slash}OC.1C)-Pad17)") (class "Default")
      (node (ref "IC1") (pin "17") (pinfunction "PB7(PCINT7/OC.0A/OC.1C)_17") (pintype "bidirectional"))
    )
    (net (code "61") (name "unconnected-(IC1-PC0(A8)-Pad35)") (class "Default")
      (node (ref "IC1") (pin "35") (pinfunction "PC0(A8)_35") (pintype "bidirectional"))
    )
    (net (code "62") (name "unconnected-(IC1-PC1(A9)-Pad36)") (class "Default")
      (node (ref "IC1") (pin "36") (pinfunction "PC1(A9)_36") (pintype "bidirectional"))
    )
    (net (code "63") (name "unconnected-(IC1-PC2(A10)-Pad37)") (class "Default")
      (node (ref "IC1") (pin "37") (pinfunction "PC2(A10)_37") (pintype "bidirectional"))
    )
    (net (code "64") (name "unconnected-(IC1-PC3(A11{slash}T.3)-Pad38)") (class "Default")
      (node (ref "IC1") (pin "38") (pinfunction "PC3(A11/T.3)_38") (pintype "bidirectional"))
    )
    (net (code "65") (name "unconnected-(IC1-PC4(A12{slash}OC.3C)-Pad39)") (class "Default")
      (node (ref "IC1") (pin "39") (pinfunction "PC4(A12/OC.3C)_39") (pintype "bidirectional"))
    )
    (net (code "66") (name "unconnected-(IC1-PC5(A13{slash}OC.3B)-Pad40)") (class "Default")
      (node (ref "IC1") (pin "40") (pinfunction "PC5(A13/OC.3B)_40") (pintype "bidirectional"))
    )
    (net (code "67") (name "unconnected-(IC1-PC6(A14{slash}OC.3A)-Pad41)") (class "Default")
      (node (ref "IC1") (pin "41") (pinfunction "PC6(A14/OC.3A)_41") (pintype "bidirectional"))
    )
    (net (code "68") (name "unconnected-(IC1-PC7(A15{slash}IC.3{slash}CLK0)-Pad42)") (class "Default")
      (node (ref "IC1") (pin "42") (pinfunction "PC7(A15/IC.3/CLK0)_42") (pintype "bidirectional"))
    )
    (net (code "69") (name "unconnected-(IC1-PD4(ICP1)-Pad29)") (class "Default")
      (node (ref "IC1") (pin "29") (pinfunction "PD4(ICP1)_29") (pintype "bidirectional"))
    )
    (net (code "70") (name "unconnected-(IC1-PD5(XCK1)-Pad30)") (class "Default")
      (node (ref "IC1") (pin "30") (pinfunction "PD5(XCK1)_30") (pintype "bidirectional"))
    )
    (net (code "71") (name "unconnected-(IC1-PE0({slash}WR)-Pad33)") (class "Default")
      (node (ref "IC1") (pin "33") (pinfunction "PE0(/WR)_33") (pintype "bidirectional"))
    )
    (net (code "72") (name "unconnected-(IC1-PE1({slash}RD)-Pad34)") (class "Default")
      (node (ref "IC1") (pin "34") (pinfunction "PE1(/RD)_34") (pintype "bidirectional"))
    )
    (net (code "73") (name "unconnected-(IC1-PE3(IUID)-Pad9)") (class "Default")
      (node (ref "IC1") (pin "9") (pinfunction "PE3(IUID)_9") (pintype "bidirectional"))
    )
    (net (code "74") (name "unconnected-(IC1-PE4(INT4{slash}TOSC1)-Pad18)") (class "Default")
      (node (ref "IC1") (pin "18") (pinfunction "PE4(INT4/TOSC1)_18") (pintype "bidirectional"))
    )
    (net (code "75") (name "unconnected-(IC1-PE5(INT5{slash}TOSC2)-Pad19)") (class "Default")
      (node (ref "IC1") (pin "19") (pinfunction "PE5(INT5/TOSC2)_19") (pintype "bidirectional"))
    )
    (net (code "76") (name "unconnected-(IC1-PE6(INT6{slash}AIN0)-Pad1)") (class "Default")
      (node (ref "IC1") (pin "1") (pinfunction "PE6(INT6/AIN0)_1") (pintype "bidirectional"))
    )
    (net (code "77") (name "unconnected-(IC1-PE7(INT7{slash}AIN1{slash}UVCON)-Pad2)") (class "Default")
      (node (ref "IC1") (pin "2") (pinfunction "PE7(INT7/AIN1/UVCON)_2") (pintype "bidirectional"))
    )
    (net (code "78") (name "unconnected-(IC1-PF2(ADC2)-Pad59)") (class "Default")
      (node (ref "IC1") (pin "59") (pinfunction "PF2(ADC2)_59") (pintype "bidirectional"))
    )
    (net (code "79") (name "unconnected-(IC1-PF3(ADC3)-Pad58)") (class "Default")
      (node (ref "IC1") (pin "58") (pinfunction "PF3(ADC3)_58") (pintype "bidirectional"))
    )
    (net (code "80") (name "unconnected-(IC3-INT1-Pad8)") (class "Default")
      (node (ref "IC3") (pin "8") (pinfunction "INT1_8") (pintype "bidirectional"))
    )
    (net (code "81") (name "unconnected-(IC3-INT2-Pad9)") (class "Default")
      (node (ref "IC3") (pin "9") (pinfunction "INT2_9") (pintype "bidirectional"))
    )
    (net (code "82") (name "unconnected-(IC3-NC-Pad3)") (class "Default")
      (node (ref "IC3") (pin "3") (pinfunction "NC_3") (pintype "bidirectional"))
    )
    (net (code "83") (name "unconnected-(IC3-NC-Pad10)") (class "Default")
      (node (ref "IC3") (pin "10") (pinfunction "NC_10") (pintype "bidirectional"))
    )
    (net (code "84") (name "unconnected-(IC3-NC-Pad11)") (class "Default")
      (node (ref "IC3") (pin "11") (pinfunction "NC_11") (pintype "bidirectional"))
    )
    (net (code "85") (name "unconnected-(IC4-DRDY-Pad15)") (class "Default")
      (node (ref "IC4") (pin "15") (pinfunction "DRDY_15") (pintype "bidirectional"))
    )
    (net (code "86") (name "unconnected-(IC5-INT-Pad12)") (class "Default")
      (node (ref "IC5") (pin "12") (pinfunction "INT_12") (pintype "bidirectional"))
    )
    (net (code "87") (name "unconnected-(IC6-DM3-Pad19)") (class "Default")
      (node (ref "IC6") (pin "19") (pinfunction "DM3_19") (pintype "bidirectional"))
    )
    (net (code "88") (name "unconnected-(IC6-DP3-Pad20)") (class "Default")
      (node (ref "IC6") (pin "20") (pinfunction "DP3_20") (pintype "bidirectional"))
    )
    (net (code "89") (name "unconnected-(IC6-EECLK-Pad5)") (class "Default")
      (node (ref "IC6") (pin "5") (pinfunction "EECLK_5") (pintype "output"))
    )
    (net (code "90") (name "unconnected-(IC6-SUSPND-Pad32)") (class "Default")
      (node (ref "IC6") (pin "32") (pinfunction "SUSPND_32") (pintype "output"))
    )
    (net (code "91") (name "unconnected-(IC6-~{OVRCUR3}-Pad18)") (class "Default")
      (node (ref "IC6") (pin "18") (pinfunction "~{OVRCUR3}_18") (pintype "input"))
    )
    (net (code "92") (name "unconnected-(IC6-~{PWRON1}-Pad9)") (class "Default")
      (node (ref "IC6") (pin "9") (pinfunction "~{PWRON1}_9") (pintype "output"))
    )
    (net (code "93") (name "unconnected-(IC6-~{PWRON2}-Pad13)") (class "Default")
      (node (ref "IC6") (pin "13") (pinfunction "~{PWRON2}_13") (pintype "output"))
    )
    (net (code "94") (name "unconnected-(IC6-~{PWRON3}-Pad17)") (class "Default")
      (node (ref "IC6") (pin "17") (pinfunction "~{PWRON3}_17") (pintype "output"))
    )
    (net (code "95") (name "unconnected-(JTAG-Pad7)") (class "Default")
      (node (ref "JTAG") (pin "7") (pinfunction "7_7") (pintype "passive"))
    )
    (net (code "96") (name "unconnected-(JTAG-Pad8)") (class "Default")
      (node (ref "JTAG") (pin "8") (pinfunction "8_8") (pintype "passive"))
    )
    (net (code "97") (name "unconnected-(X1-Pad4)") (class "Default")
      (node (ref "X1") (pin "4") (pinfunction "4_4") (pintype "passive"))
    )
  )
)
